# Memory_SRAM.net
KiCad netlist of a schematic drawn in Altium Designer
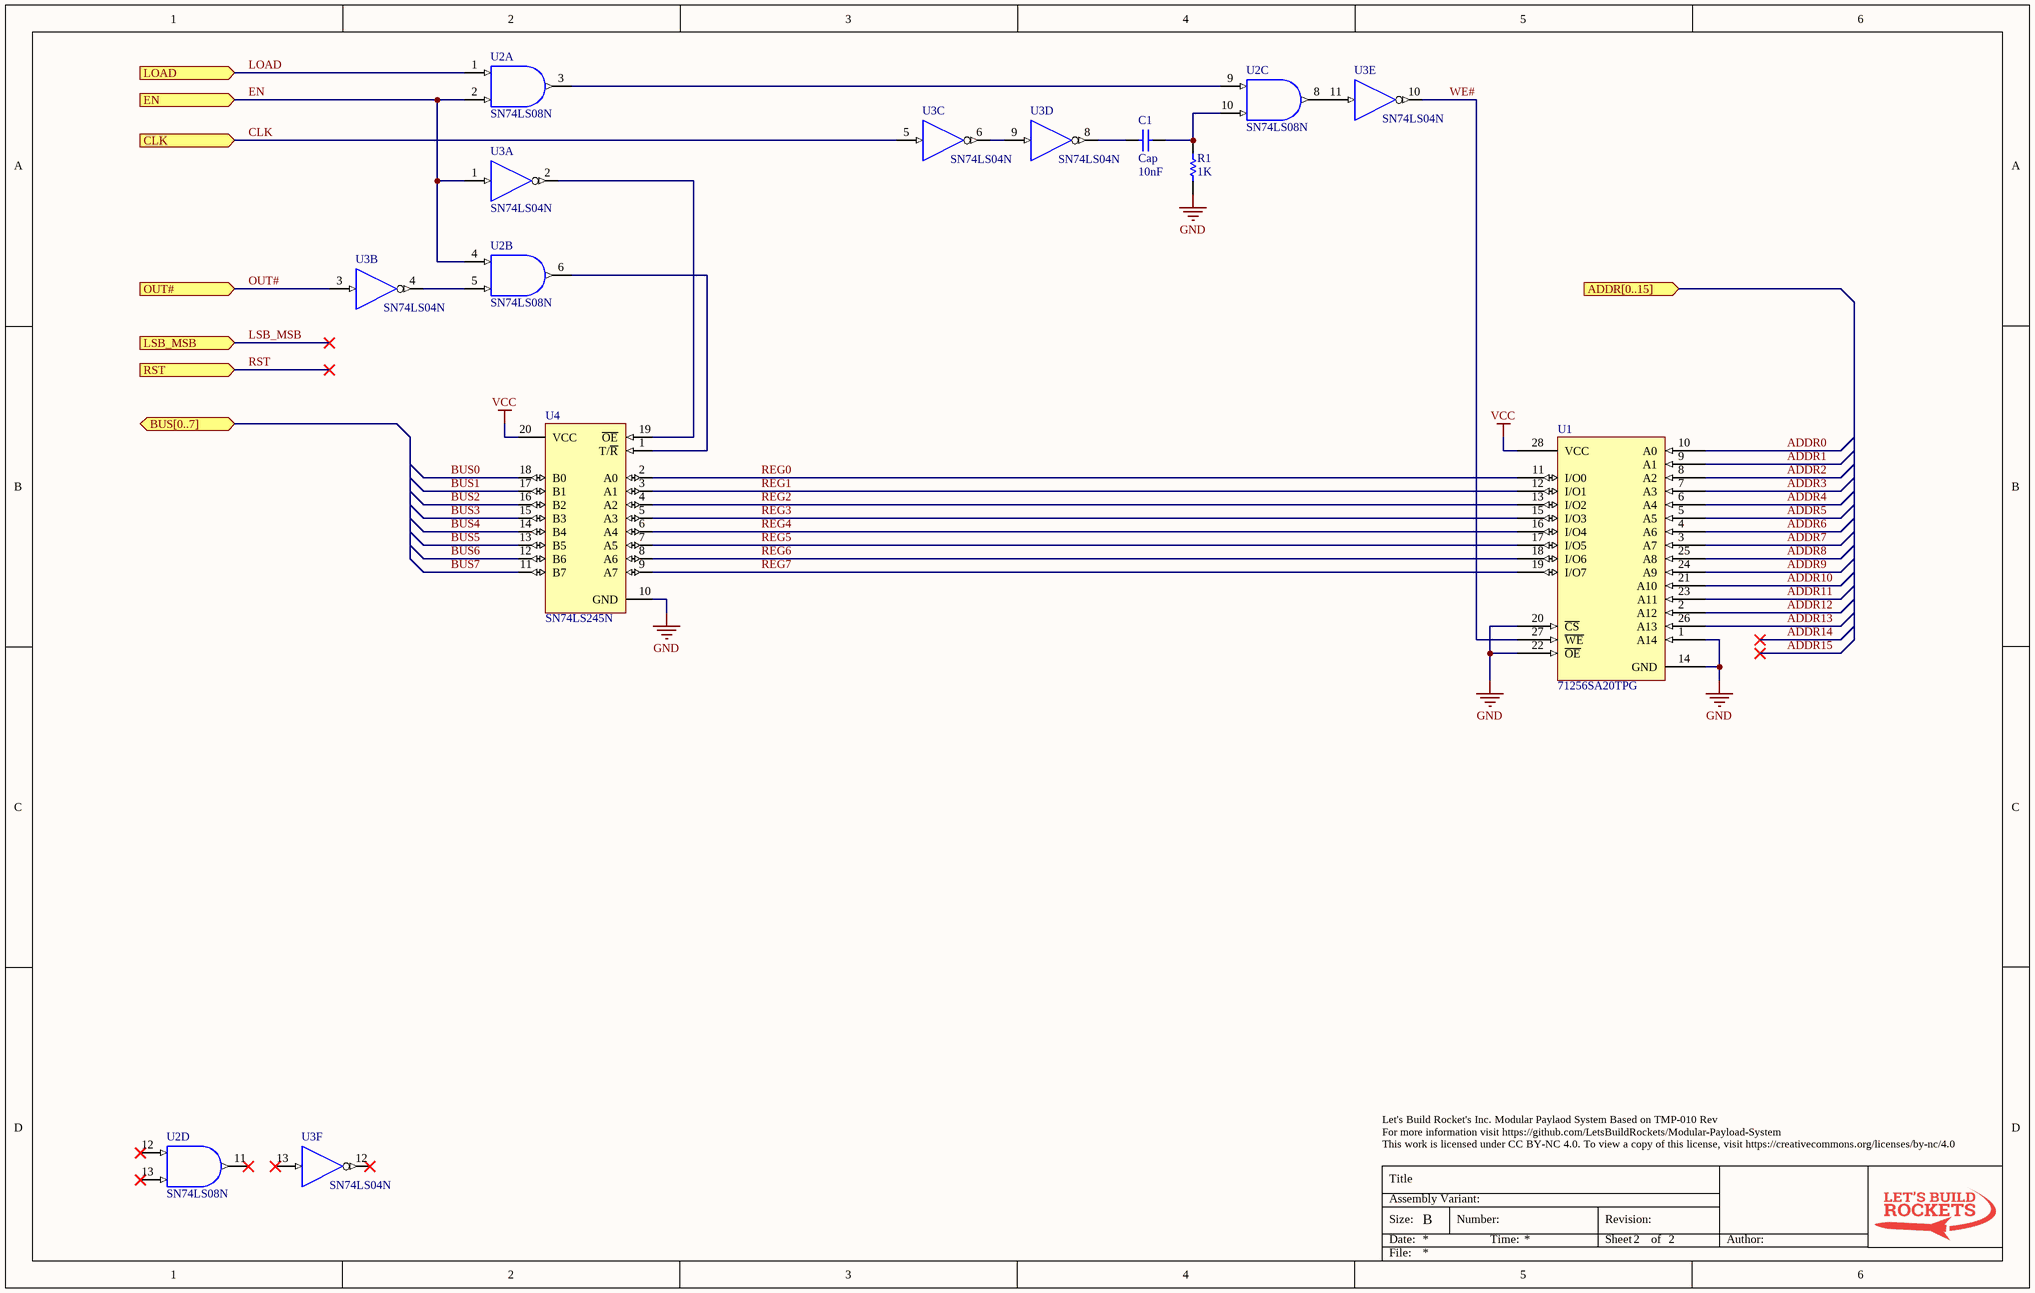
[diagram p0: Memory_SRAM.SchDoc]

(export (version "E")
  (design (tool "Eeschema 10.0.6"))
  (components
    (comp (ref "C1")
      (value "Cap")
      (footprint "RAD-0.3")
      (description "Capacitor")
      (fields (field (name "ALTIUM_VALUE") "10nF") (field (name "PUBLISHER") "Altium Limited"))
      (libsource (lib "Miscellaneous Devices") (part "Cap"))
    )
    (comp (ref "R1")
      (value "1K")
      (footprint "AXIAL-0.3")
      (description "Resistor")
      (fields (field (name "Comment") "Res1") (field (name "PUBLISHER") "Altium Limited"))
      (libsource (lib "Miscellaneous Devices") (part "Res1"))
    )
    (comp (ref "U1")
      (value "71256SA20TPG")
      (footprint "JT028")
      (libsource (lib "Schlib1") (part "71256SA20TPG"))
    )
    (comp (ref "U2")
      (value "SN74LS08N")
      (footprint "N014")
      (description "Quadruple 2-Input Positive-AND Gate")
      (fields (field (name "PUBLISHER") "Altium Limited"))
      (libsource (lib "TI Logic Gate 2") (part "SN74LS08N"))
    )
    (comp (ref "U3")
      (value "SN74LS04N")
      (footprint "N014")
      (description "Hex Inverter")
      (fields (field (name "PUBLISHER") "Altium Limited"))
      (libsource (lib "TI Logic Gate 2") (part "SN74LS04N"))
    )
    (comp (ref "U4")
      (value "SN74LS245N")
      (footprint "N020")
      (description "Octal Bus Transceiver with 3-State Outputs")
      (fields (field (name "PUBLISHER") "Altium Limited"))
      (libsource (lib "TI Interface 8-Bit Line Transceiver") (part "SN74LS245N"))
    )
  )
  (nets
    (net (code "1") (name "/ADDR0") (class "Default")
      (node (ref "U1") (pin "10") (pinfunction "A0_10") (pintype "input"))
    )
    (net (code "2") (name "/ADDR1") (class "Default")
      (node (ref "U1") (pin "9") (pinfunction "A1_9") (pintype "input"))
    )
    (net (code "3") (name "/ADDR2") (class "Default")
      (node (ref "U1") (pin "8") (pinfunction "A2_8") (pintype "input"))
    )
    (net (code "4") (name "/ADDR3") (class "Default")
      (node (ref "U1") (pin "7") (pinfunction "A3_7") (pintype "input"))
    )
    (net (code "5") (name "/ADDR4") (class "Default")
      (node (ref "U1") (pin "6") (pinfunction "A4_6") (pintype "input"))
    )
    (net (code "6") (name "/ADDR5") (class "Default")
      (node (ref "U1") (pin "5") (pinfunction "A5_5") (pintype "input"))
    )
    (net (code "7") (name "/ADDR6") (class "Default")
      (node (ref "U1") (pin "4") (pinfunction "A6_4") (pintype "input"))
    )
    (net (code "8") (name "/ADDR7") (class "Default")
      (node (ref "U1") (pin "3") (pinfunction "A7_3") (pintype "input"))
    )
    (net (code "9") (name "/ADDR8") (class "Default")
      (node (ref "U1") (pin "25") (pinfunction "A8_25") (pintype "input"))
    )
    (net (code "10") (name "/ADDR9") (class "Default")
      (node (ref "U1") (pin "24") (pinfunction "A9_24") (pintype "input"))
    )
    (net (code "11") (name "/ADDR10") (class "Default")
      (node (ref "U1") (pin "21") (pinfunction "A10_21") (pintype "input"))
    )
    (net (code "12") (name "/ADDR11") (class "Default")
      (node (ref "U1") (pin "23") (pinfunction "A11_23") (pintype "input"))
    )
    (net (code "13") (name "/ADDR12") (class "Default")
      (node (ref "U1") (pin "2") (pinfunction "A12_2") (pintype "input"))
    )
    (net (code "14") (name "/ADDR13") (class "Default")
      (node (ref "U1") (pin "26") (pinfunction "A13_26") (pintype "input"))
    )
    (net (code "18") (name "/BUS0") (class "Default")
      (node (ref "U4") (pin "18") (pinfunction "B0_18") (pintype "bidirectional"))
    )
    (net (code "19") (name "/BUS1") (class "Default")
      (node (ref "U4") (pin "17") (pinfunction "B1_17") (pintype "bidirectional"))
    )
    (net (code "20") (name "/BUS2") (class "Default")
      (node (ref "U4") (pin "16") (pinfunction "B2_16") (pintype "bidirectional"))
    )
    (net (code "21") (name "/BUS3") (class "Default")
      (node (ref "U4") (pin "15") (pinfunction "B3_15") (pintype "bidirectional"))
    )
    (net (code "22") (name "/BUS4") (class "Default")
      (node (ref "U4") (pin "14") (pinfunction "B4_14") (pintype "bidirectional"))
    )
    (net (code "23") (name "/BUS5") (class "Default")
      (node (ref "U4") (pin "13") (pinfunction "B5_13") (pintype "bidirectional"))
    )
    (net (code "24") (name "/BUS6") (class "Default")
      (node (ref "U4") (pin "12") (pinfunction "B6_12") (pintype "bidirectional"))
    )
    (net (code "25") (name "/BUS7") (class "Default")
      (node (ref "U4") (pin "11") (pinfunction "B7_11") (pintype "bidirectional"))
    )
    (net (code "27") (name "/CLK") (class "Default")
      (node (ref "U3") (pin "5") (pinfunction "A_5") (pintype "input"))
    )
    (net (code "28") (name "/EN") (class "Default")
      (node (ref "U2") (pin "2") (pinfunction "B_2") (pintype "input"))
      (node (ref "U2") (pin "4") (pinfunction "A_4") (pintype "input"))
      (node (ref "U3") (pin "1") (pinfunction "A_1") (pintype "input"))
    )
    (net (code "29") (name "/LOAD") (class "Default")
      (node (ref "U2") (pin "1") (pinfunction "A_1") (pintype "input"))
    )
    (net (code "31") (name "/OUT#") (class "Default")
      (node (ref "U3") (pin "3") (pinfunction "A_3") (pintype "input"))
    )
    (net (code "32") (name "/REG0") (class "Default")
      (node (ref "U1") (pin "11") (pinfunction "I/O0_11") (pintype "bidirectional"))
      (node (ref "U4") (pin "2") (pinfunction "A0_2") (pintype "bidirectional"))
    )
    (net (code "33") (name "/REG1") (class "Default")
      (node (ref "U1") (pin "12") (pinfunction "I/O1_12") (pintype "bidirectional"))
      (node (ref "U4") (pin "3") (pinfunction "A1_3") (pintype "bidirectional"))
    )
    (net (code "34") (name "/REG2") (class "Default")
      (node (ref "U1") (pin "13") (pinfunction "I/O2_13") (pintype "bidirectional"))
      (node (ref "U4") (pin "4") (pinfunction "A2_4") (pintype "bidirectional"))
    )
    (net (code "35") (name "/REG3") (class "Default")
      (node (ref "U1") (pin "15") (pinfunction "I/O3_15") (pintype "bidirectional"))
      (node (ref "U4") (pin "5") (pinfunction "A3_5") (pintype "bidirectional"))
    )
    (net (code "36") (name "/REG4") (class "Default")
      (node (ref "U1") (pin "16") (pinfunction "I/O4_16") (pintype "bidirectional"))
      (node (ref "U4") (pin "6") (pinfunction "A4_6") (pintype "bidirectional"))
    )
    (net (code "37") (name "/REG5") (class "Default")
      (node (ref "U1") (pin "17") (pinfunction "I/O5_17") (pintype "bidirectional"))
      (node (ref "U4") (pin "7") (pinfunction "A5_7") (pintype "bidirectional"))
    )
    (net (code "38") (name "/REG6") (class "Default")
      (node (ref "U1") (pin "18") (pinfunction "I/O6_18") (pintype "bidirectional"))
      (node (ref "U4") (pin "8") (pinfunction "A6_8") (pintype "bidirectional"))
    )
    (net (code "39") (name "/REG7") (class "Default")
      (node (ref "U1") (pin "19") (pinfunction "I/O7_19") (pintype "bidirectional"))
      (node (ref "U4") (pin "9") (pinfunction "A7_9") (pintype "bidirectional"))
    )
    (net (code "41") (name "/WE#") (class "Default")
      (node (ref "U1") (pin "27") (pinfunction "~{WE}_27") (pintype "input"))
      (node (ref "U3") (pin "10") (pinfunction "Y_10") (pintype "output"))
    )
    (net (code "42") (name "GND") (class "Default")
      (node (ref "R1") (pin "1") (pinfunction "1_1") (pintype "passive"))
      (node (ref "U1") (pin "1") (pinfunction "A14_1") (pintype "input"))
      (node (ref "U1") (pin "14") (pinfunction "GND_14") (pintype "power_in"))
      (node (ref "U1") (pin "20") (pinfunction "~{CS}_20") (pintype "input"))
      (node (ref "U1") (pin "22") (pinfunction "~{OE}_22") (pintype "input"))
      (node (ref "U2") (pin "7") (pinfunction "GND_7") (pintype "power_in"))
      (node (ref "U3") (pin "7") (pinfunction "GND_7") (pintype "power_in"))
      (node (ref "U4") (pin "10") (pinfunction "GND_10") (pintype "power_in"))
    )
    (net (code "43") (name "Net-(U2A-Y)") (class "Default")
      (node (ref "U2") (pin "3") (pinfunction "Y_3") (pintype "output"))
      (node (ref "U2") (pin "9") (pinfunction "A_9") (pintype "input"))
    )
    (net (code "44") (name "Net-(U2B-B)") (class "Default")
      (node (ref "U2") (pin "5") (pinfunction "B_5") (pintype "input"))
      (node (ref "U3") (pin "4") (pinfunction "Y_4") (pintype "output"))
    )
    (net (code "45") (name "Net-(U2B-Y)") (class "Default")
      (node (ref "U2") (pin "6") (pinfunction "Y_6") (pintype "output"))
      (node (ref "U4") (pin "1") (pinfunction "T/~{R}_1") (pintype "input"))
    )
    (net (code "46") (name "Net-(U2C-B)") (class "Default")
      (node (ref "C1") (pin "1") (pinfunction "1_1") (pintype "passive"))
      (node (ref "R1") (pin "2") (pinfunction "2_2") (pintype "passive"))
      (node (ref "U2") (pin "10") (pinfunction "B_10") (pintype "input"))
    )
    (net (code "47") (name "Net-(U2C-Y)") (class "Default")
      (node (ref "U2") (pin "8") (pinfunction "Y_8") (pintype "output"))
      (node (ref "U3") (pin "11") (pinfunction "A_11") (pintype "input"))
    )
    (net (code "48") (name "Net-(U3A-Y)") (class "Default")
      (node (ref "U3") (pin "2") (pinfunction "Y_2") (pintype "output"))
      (node (ref "U4") (pin "19") (pinfunction "~{OE}_19") (pintype "input"))
    )
    (net (code "49") (name "Net-(U3C-Y)") (class "Default")
      (node (ref "U3") (pin "6") (pinfunction "Y_6") (pintype "output"))
      (node (ref "U3") (pin "9") (pinfunction "A_9") (pintype "input"))
    )
    (net (code "50") (name "Net-(U3D-Y)") (class "Default")
      (node (ref "C1") (pin "2") (pinfunction "2_2") (pintype "passive"))
      (node (ref "U3") (pin "8") (pinfunction "Y_8") (pintype "output"))
    )
    (net (code "51") (name "VCC") (class "Default")
      (node (ref "U1") (pin "28") (pinfunction "VCC_28") (pintype "power_in"))
      (node (ref "U2") (pin "14") (pinfunction "VCC_14") (pintype "power_in"))
      (node (ref "U3") (pin "14") (pinfunction "VCC_14") (pintype "power_in"))
      (node (ref "U4") (pin "20") (pinfunction "VCC_20") (pintype "power_in"))
    )
    (net (code "52") (name "unconnected-(U2D-A-Pad12)") (class "Default")
      (node (ref "U2") (pin "12") (pinfunction "A_12") (pintype "input+no_connect"))
    )
    (net (code "53") (name "unconnected-(U2D-B-Pad13)") (class "Default")
      (node (ref "U2") (pin "13") (pinfunction "B_13") (pintype "input+no_connect"))
    )
    (net (code "54") (name "unconnected-(U2D-Y-Pad11)") (class "Default")
      (node (ref "U2") (pin "11") (pinfunction "Y_11") (pintype "output+no_connect"))
    )
    (net (code "55") (name "unconnected-(U3F-A-Pad13)") (class "Default")
      (node (ref "U3") (pin "13") (pinfunction "A_13") (pintype "input+no_connect"))
    )
    (net (code "56") (name "unconnected-(U3F-Y-Pad12)") (class "Default")
      (node (ref "U3") (pin "12") (pinfunction "Y_12") (pintype "output+no_connect"))
    )
  )
)
